# NanoEls.net
KiCad netlist of a schematic drawn in EasyEDA
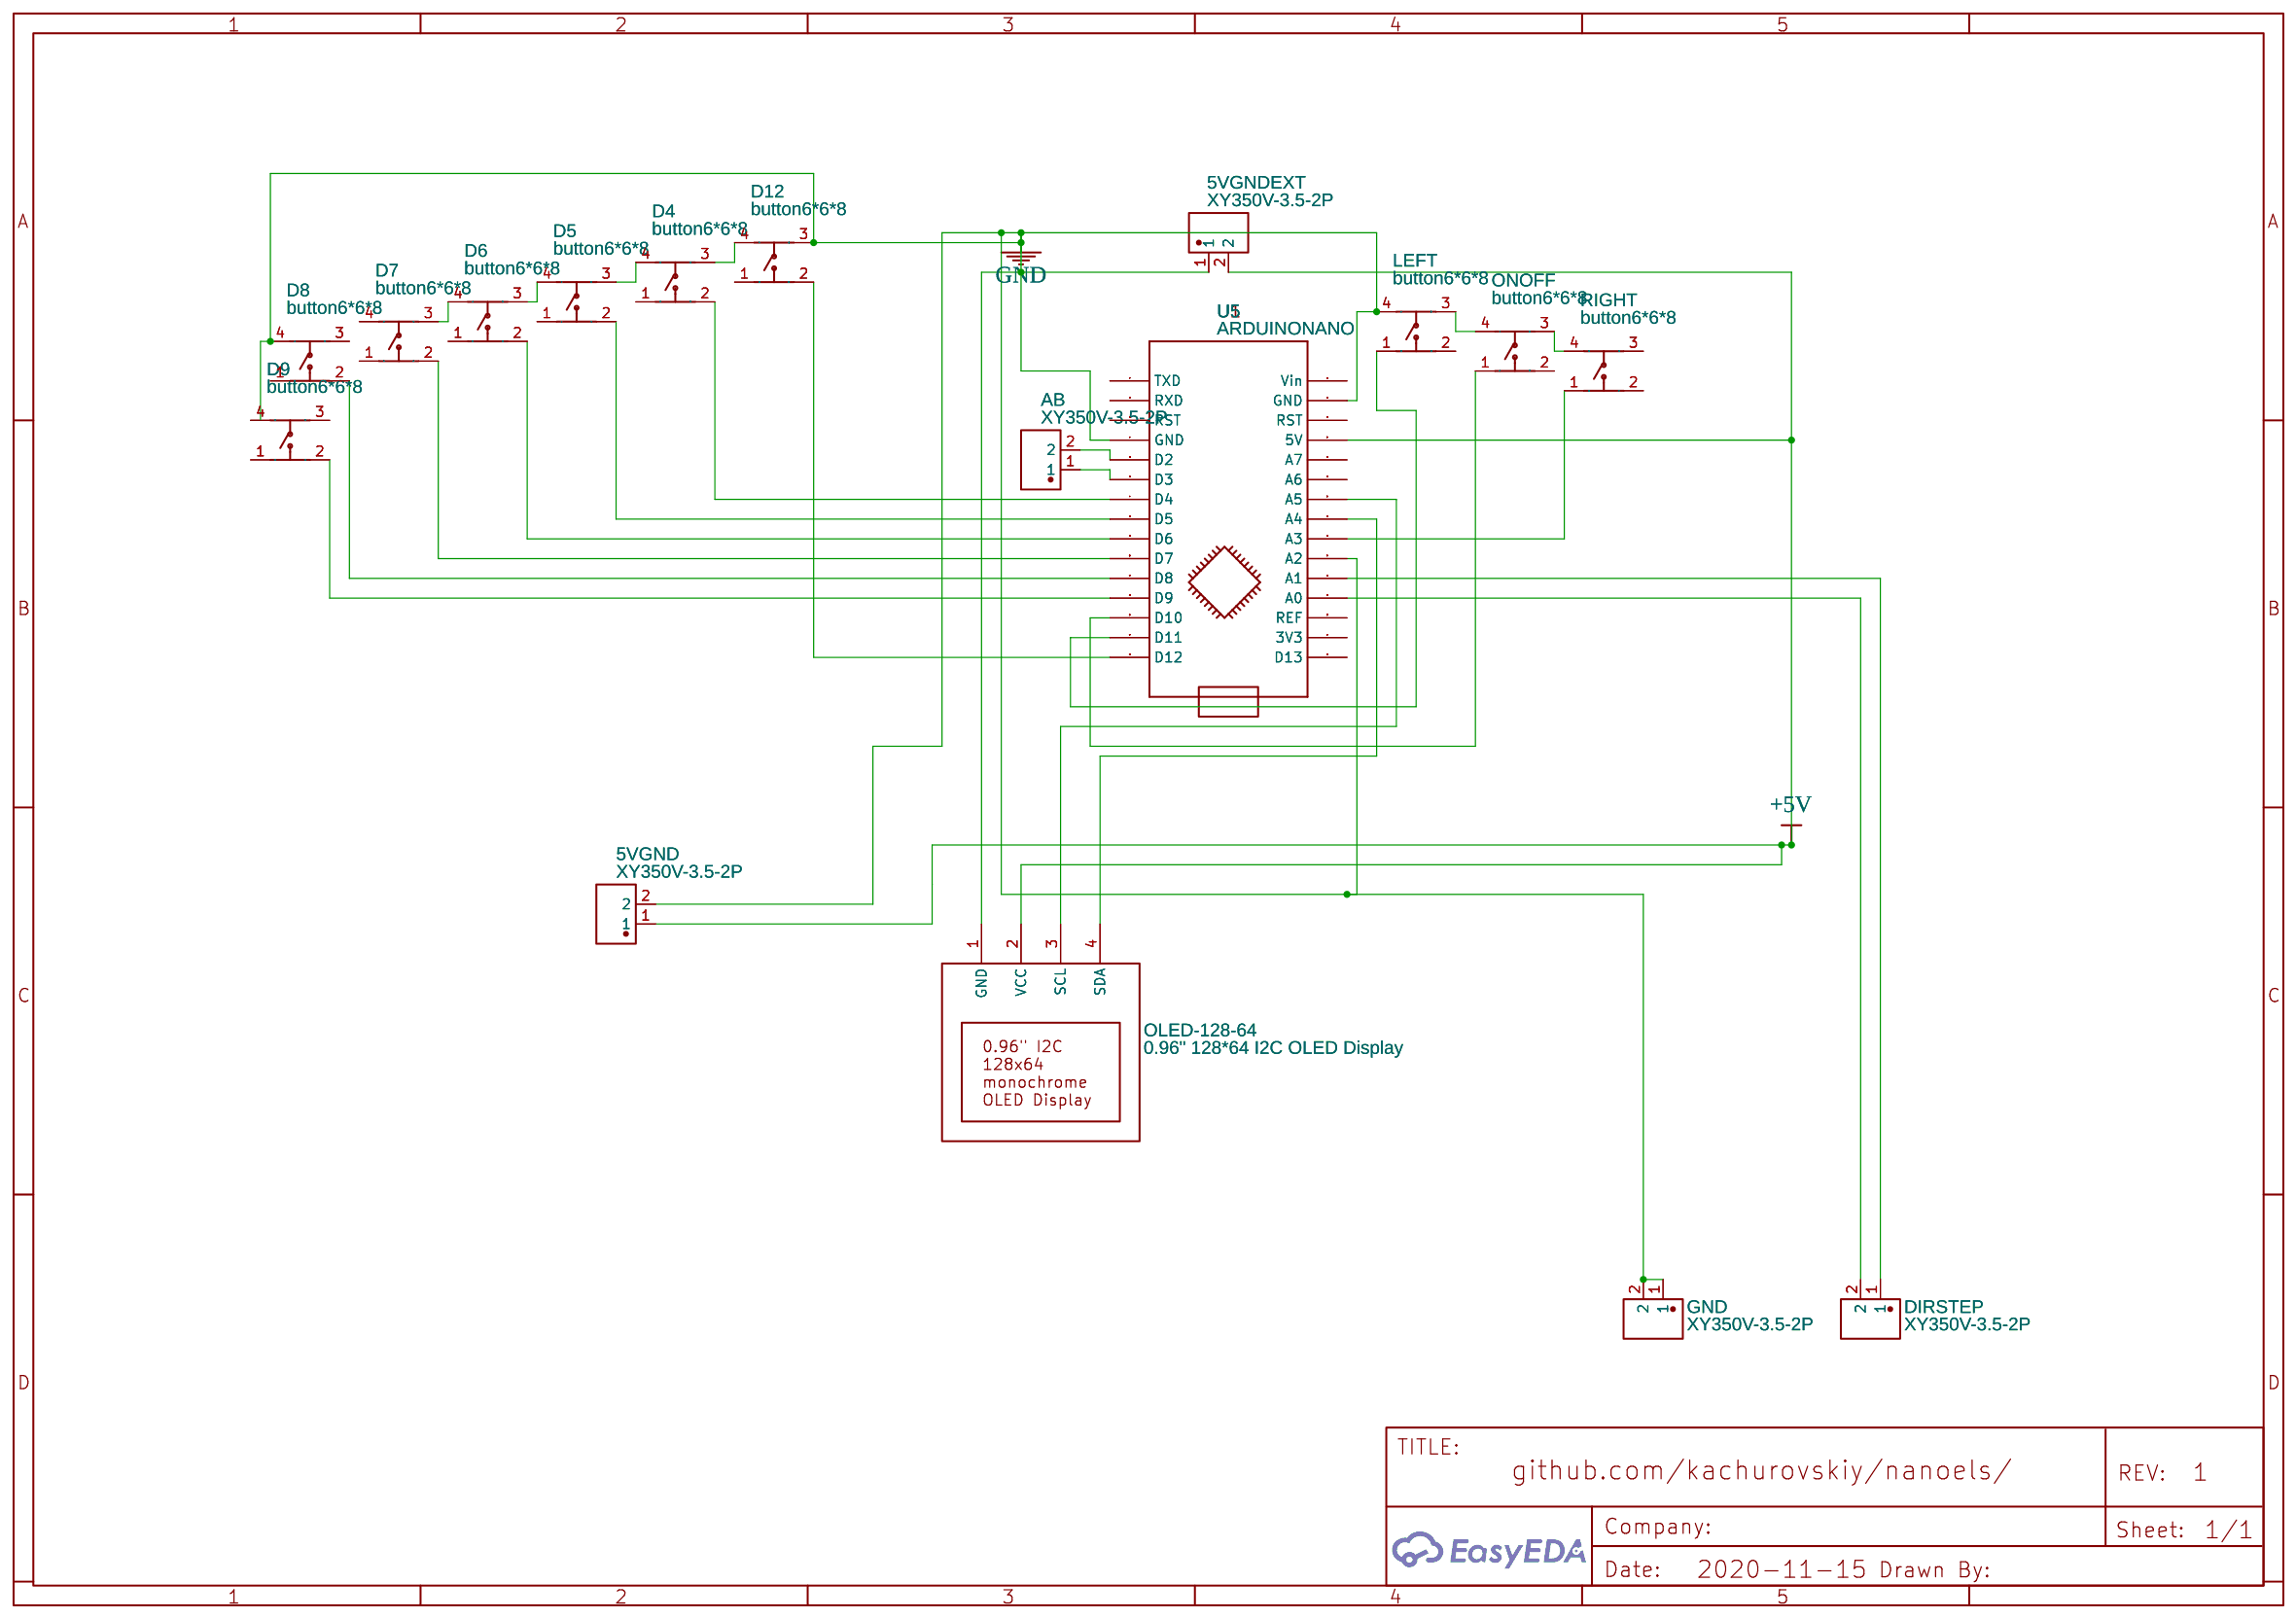
[diagram p0: schematic sheet]

(export (version "E")
  (design (tool "Eeschema 10.0.6"))
  (components
    (comp (ref "5VGND")
      (value "XY350V-3.5-2P")
      (fields (field (name "BOM_Supplier Part") "C784942"))
      (libsource (lib "") (part "XY350V-3.5-2P"))
    )
    (comp (ref "5VGNDEXT")
      (value "XY350V-3.5-2P")
      (fields (field (name "BOM_Supplier Part") "C784942"))
      (libsource (lib "") (part "XY350V-3.5-2P_1"))
    )
    (comp (ref "AB")
      (value "XY350V-3.5-2P")
      (fields (field (name "BOM_Supplier Part") "C784942"))
      (libsource (lib "") (part "XY350V-3.5-2P_4"))
    )
    (comp (ref "D4")
      (value "button6*6*8")
      (fields (field (name "BOM_Supplier Part") "C59982"))
      (libsource (lib "") (part "button6*6*8"))
    )
    (comp (ref "D5")
      (value "button6*6*8")
      (fields (field (name "BOM_Supplier Part") "C59982"))
      (libsource (lib "") (part "button6*6*8"))
    )
    (comp (ref "D6")
      (value "button6*6*8")
      (fields (field (name "BOM_Supplier Part") "C59982"))
      (libsource (lib "") (part "button6*6*8"))
    )
    (comp (ref "D7")
      (value "button6*6*8")
      (fields (field (name "BOM_Supplier Part") "C59982"))
      (libsource (lib "") (part "button6*6*8"))
    )
    (comp (ref "D8")
      (value "button6*6*8")
      (fields (field (name "BOM_Supplier Part") "C59982"))
      (libsource (lib "") (part "button6*6*8"))
    )
    (comp (ref "D9")
      (value "button6*6*8")
      (fields (field (name "BOM_Supplier Part") "C59982"))
      (libsource (lib "") (part "button6*6*8"))
    )
    (comp (ref "D12")
      (value "button6*6*8")
      (fields (field (name "BOM_Supplier Part") "C59982"))
      (libsource (lib "") (part "button6*6*8"))
    )
    (comp (ref "DIRSTEP")
      (value "XY350V-3.5-2P")
      (fields (field (name "BOM_Supplier Part") "C784942"))
      (libsource (lib "") (part "XY350V-3.5-2P_3"))
    )
    (comp (ref "GND")
      (value "XY350V-3.5-2P")
      (fields (field (name "BOM_Supplier Part") "C784942"))
      (libsource (lib "") (part "XY350V-3.5-2P_2"))
    )
    (comp (ref "LEFT")
      (value "button6*6*8")
      (fields (field (name "BOM_Supplier Part") "C59982"))
      (libsource (lib "") (part "button6*6*8_3"))
    )
    (comp (ref "OLED-128-64")
      (value "0.96\" 128*64 I2C OLED Display")
      (libsource (lib "") (part "0.96{dblquote} 128*64 I2C OLED Display"))
    )
    (comp (ref "ONOFF")
      (value "button6*6*8")
      (fields (field (name "BOM_Supplier Part") "C59982"))
      (libsource (lib "") (part "button6*6*8_2"))
    )
    (comp (ref "RIGHT")
      (value "button6*6*8")
      (fields (field (name "BOM_Supplier Part") "C59982"))
      (libsource (lib "") (part "button6*6*8_1"))
    )
    (comp (ref "U5")
      (value "ARDUINONANO")
      (fields (field (name "BOM_Manufacturer Part") "arduino_nano1"))
      (libsource (lib "") (part "ARDUINONANO"))
    )
  )
  (nets
    (net (code "1") (name "+5V") (class "Default")
      (node (ref "5VGND") (pin "1") (pinfunction "1_1") (pintype "unspecified"))
      (node (ref "5VGNDEXT") (pin "2") (pinfunction "2_2") (pintype "unspecified"))
      (node (ref "OLED-128-64") (pin "2") (pinfunction "VCC_2") (pintype "unspecified"))
      (node (ref "U5") (pin "27") (pinfunction "5V_27") (pintype "unspecified"))
    )
    (net (code "2") (name "GND") (class "Default")
      (node (ref "5VGND") (pin "2") (pinfunction "2_2") (pintype "unspecified"))
      (node (ref "5VGNDEXT") (pin "1") (pinfunction "1_1") (pintype "unspecified"))
      (node (ref "D12") (pin "3") (pinfunction "3_3") (pintype "unspecified"))
      (node (ref "D8") (pin "4") (pinfunction "4_4") (pintype "unspecified"))
      (node (ref "D9") (pin "4") (pinfunction "4_4") (pintype "unspecified"))
      (node (ref "GND") (pin "1") (pinfunction "1_1") (pintype "unspecified"))
      (node (ref "GND") (pin "2") (pinfunction "2_2") (pintype "unspecified"))
      (node (ref "LEFT") (pin "4") (pinfunction "4_4") (pintype "unspecified"))
      (node (ref "OLED-128-64") (pin "1") (pinfunction "GND_1") (pintype "unspecified"))
      (node (ref "U5") (pin "21") (pinfunction "A2_21") (pintype "unspecified"))
      (node (ref "U5") (pin "29") (pinfunction "GND_29") (pintype "unspecified"))
      (node (ref "U5") (pin "4") (pinfunction "GND_4") (pintype "unspecified"))
    )
    (net (code "3") (name "Net-(D4-Pad4)") (class "Default")
      (node (ref "D4") (pin "4") (pinfunction "4_4") (pintype "unspecified"))
      (node (ref "D5") (pin "3") (pinfunction "3_3") (pintype "unspecified"))
    )
    (net (code "4") (name "Net-(D5-Pad4)") (class "Default")
      (node (ref "D5") (pin "4") (pinfunction "4_4") (pintype "unspecified"))
      (node (ref "D6") (pin "3") (pinfunction "3_3") (pintype "unspecified"))
    )
    (net (code "5") (name "Net-(D6-Pad4)") (class "Default")
      (node (ref "D6") (pin "4") (pinfunction "4_4") (pintype "unspecified"))
      (node (ref "D7") (pin "3") (pinfunction "3_3") (pintype "unspecified"))
    )
    (net (code "6") (name "Net-(D12-Pad4)") (class "Default")
      (node (ref "D12") (pin "4") (pinfunction "4_4") (pintype "unspecified"))
      (node (ref "D4") (pin "3") (pinfunction "3_3") (pintype "unspecified"))
    )
    (net (code "7") (name "Net-(LEFT-Pad3)") (class "Default")
      (node (ref "LEFT") (pin "3") (pinfunction "3_3") (pintype "unspecified"))
      (node (ref "ONOFF") (pin "4") (pinfunction "4_4") (pintype "unspecified"))
    )
    (net (code "8") (name "Net-(OLED-128-64-SCL)") (class "Default")
      (node (ref "OLED-128-64") (pin "3") (pinfunction "SCL_3") (pintype "unspecified"))
      (node (ref "U5") (pin "24") (pinfunction "A5_24") (pintype "unspecified"))
    )
    (net (code "9") (name "Net-(OLED-128-64-SDA)") (class "Default")
      (node (ref "OLED-128-64") (pin "4") (pinfunction "SDA_4") (pintype "unspecified"))
      (node (ref "U5") (pin "23") (pinfunction "A4_23") (pintype "unspecified"))
    )
    (net (code "10") (name "Net-(ONOFF-Pad3)") (class "Default")
      (node (ref "ONOFF") (pin "3") (pinfunction "3_3") (pintype "unspecified"))
      (node (ref "RIGHT") (pin "4") (pinfunction "4_4") (pintype "unspecified"))
    )
    (net (code "11") (name "Net-(U5-A0)") (class "Default")
      (node (ref "DIRSTEP") (pin "2") (pinfunction "2_2") (pintype "unspecified"))
      (node (ref "U5") (pin "19") (pinfunction "A0_19") (pintype "unspecified"))
    )
    (net (code "12") (name "Net-(U5-A1)") (class "Default")
      (node (ref "DIRSTEP") (pin "1") (pinfunction "1_1") (pintype "unspecified"))
      (node (ref "U5") (pin "20") (pinfunction "A1_20") (pintype "unspecified"))
    )
    (net (code "13") (name "Net-(U5-A3)") (class "Default")
      (node (ref "RIGHT") (pin "1") (pinfunction "1_1") (pintype "unspecified"))
      (node (ref "U5") (pin "22") (pinfunction "A3_22") (pintype "unspecified"))
    )
    (net (code "14") (name "Net-(U5-D2)") (class "Default")
      (node (ref "AB") (pin "2") (pinfunction "2_2") (pintype "unspecified"))
      (node (ref "U5") (pin "5") (pinfunction "D2_5") (pintype "unspecified"))
    )
    (net (code "15") (name "Net-(U5-D3)") (class "Default")
      (node (ref "AB") (pin "1") (pinfunction "1_1") (pintype "unspecified"))
      (node (ref "U5") (pin "6") (pinfunction "D3_6") (pintype "unspecified"))
    )
    (net (code "16") (name "Net-(U5-D4)") (class "Default")
      (node (ref "D4") (pin "2") (pinfunction "2_2") (pintype "unspecified"))
      (node (ref "U5") (pin "7") (pinfunction "D4_7") (pintype "unspecified"))
    )
    (net (code "17") (name "Net-(U5-D5)") (class "Default")
      (node (ref "D5") (pin "2") (pinfunction "2_2") (pintype "unspecified"))
      (node (ref "U5") (pin "8") (pinfunction "D5_8") (pintype "unspecified"))
    )
    (net (code "18") (name "Net-(U5-D6)") (class "Default")
      (node (ref "D6") (pin "2") (pinfunction "2_2") (pintype "unspecified"))
      (node (ref "U5") (pin "9") (pinfunction "D6_9") (pintype "unspecified"))
    )
    (net (code "19") (name "Net-(U5-D7)") (class "Default")
      (node (ref "D7") (pin "2") (pinfunction "2_2") (pintype "unspecified"))
      (node (ref "U5") (pin "10") (pinfunction "D7_10") (pintype "unspecified"))
    )
    (net (code "20") (name "Net-(U5-D8)") (class "Default")
      (node (ref "D8") (pin "2") (pinfunction "2_2") (pintype "unspecified"))
      (node (ref "U5") (pin "11") (pinfunction "D8_11") (pintype "unspecified"))
    )
    (net (code "21") (name "Net-(U5-D9)") (class "Default")
      (node (ref "D9") (pin "2") (pinfunction "2_2") (pintype "unspecified"))
      (node (ref "U5") (pin "12") (pinfunction "D9_12") (pintype "unspecified"))
    )
    (net (code "22") (name "Net-(U5-D10)") (class "Default")
      (node (ref "ONOFF") (pin "1") (pinfunction "1_1") (pintype "unspecified"))
      (node (ref "U5") (pin "13") (pinfunction "D10_13") (pintype "unspecified"))
    )
    (net (code "23") (name "Net-(U5-D11)") (class "Default")
      (node (ref "LEFT") (pin "1") (pinfunction "1_1") (pintype "unspecified"))
      (node (ref "U5") (pin "14") (pinfunction "D11_14") (pintype "unspecified"))
    )
    (net (code "24") (name "Net-(U5-D12)") (class "Default")
      (node (ref "D12") (pin "2") (pinfunction "2_2") (pintype "unspecified"))
      (node (ref "U5") (pin "15") (pinfunction "D12_15") (pintype "unspecified"))
    )
    (net (code "25") (name "unconnected-(D4-Pad1)") (class "Default")
      (node (ref "D4") (pin "1") (pinfunction "1_1") (pintype "unspecified"))
    )
    (net (code "26") (name "unconnected-(D5-Pad1)") (class "Default")
      (node (ref "D5") (pin "1") (pinfunction "1_1") (pintype "unspecified"))
    )
    (net (code "27") (name "unconnected-(D6-Pad1)") (class "Default")
      (node (ref "D6") (pin "1") (pinfunction "1_1") (pintype "unspecified"))
    )
    (net (code "28") (name "unconnected-(D7-Pad1)") (class "Default")
      (node (ref "D7") (pin "1") (pinfunction "1_1") (pintype "unspecified"))
    )
    (net (code "29") (name "unconnected-(D7-Pad4)") (class "Default")
      (node (ref "D7") (pin "4") (pinfunction "4_4") (pintype "unspecified"))
    )
    (net (code "30") (name "unconnected-(D8-Pad1)") (class "Default")
      (node (ref "D8") (pin "1") (pinfunction "1_1") (pintype "unspecified"))
    )
    (net (code "31") (name "unconnected-(D8-Pad3)") (class "Default")
      (node (ref "D8") (pin "3") (pinfunction "3_3") (pintype "unspecified"))
    )
    (net (code "32") (name "unconnected-(D9-Pad1)") (class "Default")
      (node (ref "D9") (pin "1") (pinfunction "1_1") (pintype "unspecified"))
    )
    (net (code "33") (name "unconnected-(D9-Pad3)") (class "Default")
      (node (ref "D9") (pin "3") (pinfunction "3_3") (pintype "unspecified"))
    )
    (net (code "34") (name "unconnected-(D12-Pad1)") (class "Default")
      (node (ref "D12") (pin "1") (pinfunction "1_1") (pintype "unspecified"))
    )
    (net (code "35") (name "unconnected-(LEFT-Pad2)") (class "Default")
      (node (ref "LEFT") (pin "2") (pinfunction "2_2") (pintype "unspecified"))
    )
    (net (code "36") (name "unconnected-(ONOFF-Pad2)") (class "Default")
      (node (ref "ONOFF") (pin "2") (pinfunction "2_2") (pintype "unspecified"))
    )
    (net (code "37") (name "unconnected-(RIGHT-Pad2)") (class "Default")
      (node (ref "RIGHT") (pin "2") (pinfunction "2_2") (pintype "unspecified"))
    )
    (net (code "38") (name "unconnected-(RIGHT-Pad3)") (class "Default")
      (node (ref "RIGHT") (pin "3") (pinfunction "3_3") (pintype "unspecified"))
    )
    (net (code "39") (name "unconnected-(U5-3V3-Pad17)") (class "Default")
      (node (ref "U5") (pin "17") (pinfunction "3V3_17") (pintype "unspecified"))
    )
    (net (code "40") (name "unconnected-(U5-A6-Pad25)") (class "Default")
      (node (ref "U5") (pin "25") (pinfunction "A6_25") (pintype "unspecified"))
    )
    (net (code "41") (name "unconnected-(U5-A7-Pad26)") (class "Default")
      (node (ref "U5") (pin "26") (pinfunction "A7_26") (pintype "unspecified"))
    )
    (net (code "42") (name "unconnected-(U5-D13-Pad16)") (class "Default")
      (node (ref "U5") (pin "16") (pinfunction "D13_16") (pintype "unspecified"))
    )
    (net (code "43") (name "unconnected-(U5-REF-Pad18)") (class "Default")
      (node (ref "U5") (pin "18") (pinfunction "REF_18") (pintype "unspecified"))
    )
    (net (code "44") (name "unconnected-(U5-RST-Pad3)") (class "Default")
      (node (ref "U5") (pin "3") (pinfunction "RST_3") (pintype "unspecified"))
    )
    (net (code "45") (name "unconnected-(U5-RST-Pad28)") (class "Default")
      (node (ref "U5") (pin "28") (pinfunction "RST_28") (pintype "unspecified"))
    )
    (net (code "46") (name "unconnected-(U5-RXD-Pad2)") (class "Default")
      (node (ref "U5") (pin "2") (pinfunction "RXD_2") (pintype "unspecified"))
    )
    (net (code "47") (name "unconnected-(U5-TXD-Pad1)") (class "Default")
      (node (ref "U5") (pin "1") (pinfunction "TXD_1") (pintype "unspecified"))
    )
    (net (code "48") (name "unconnected-(U5-Vin-Pad30)") (class "Default")
      (node (ref "U5") (pin "30") (pinfunction "Vin_30") (pintype "unspecified"))
    )
  )
)
